# facedancer21.net
KiCad netlist of a schematic drawn in EAGLE
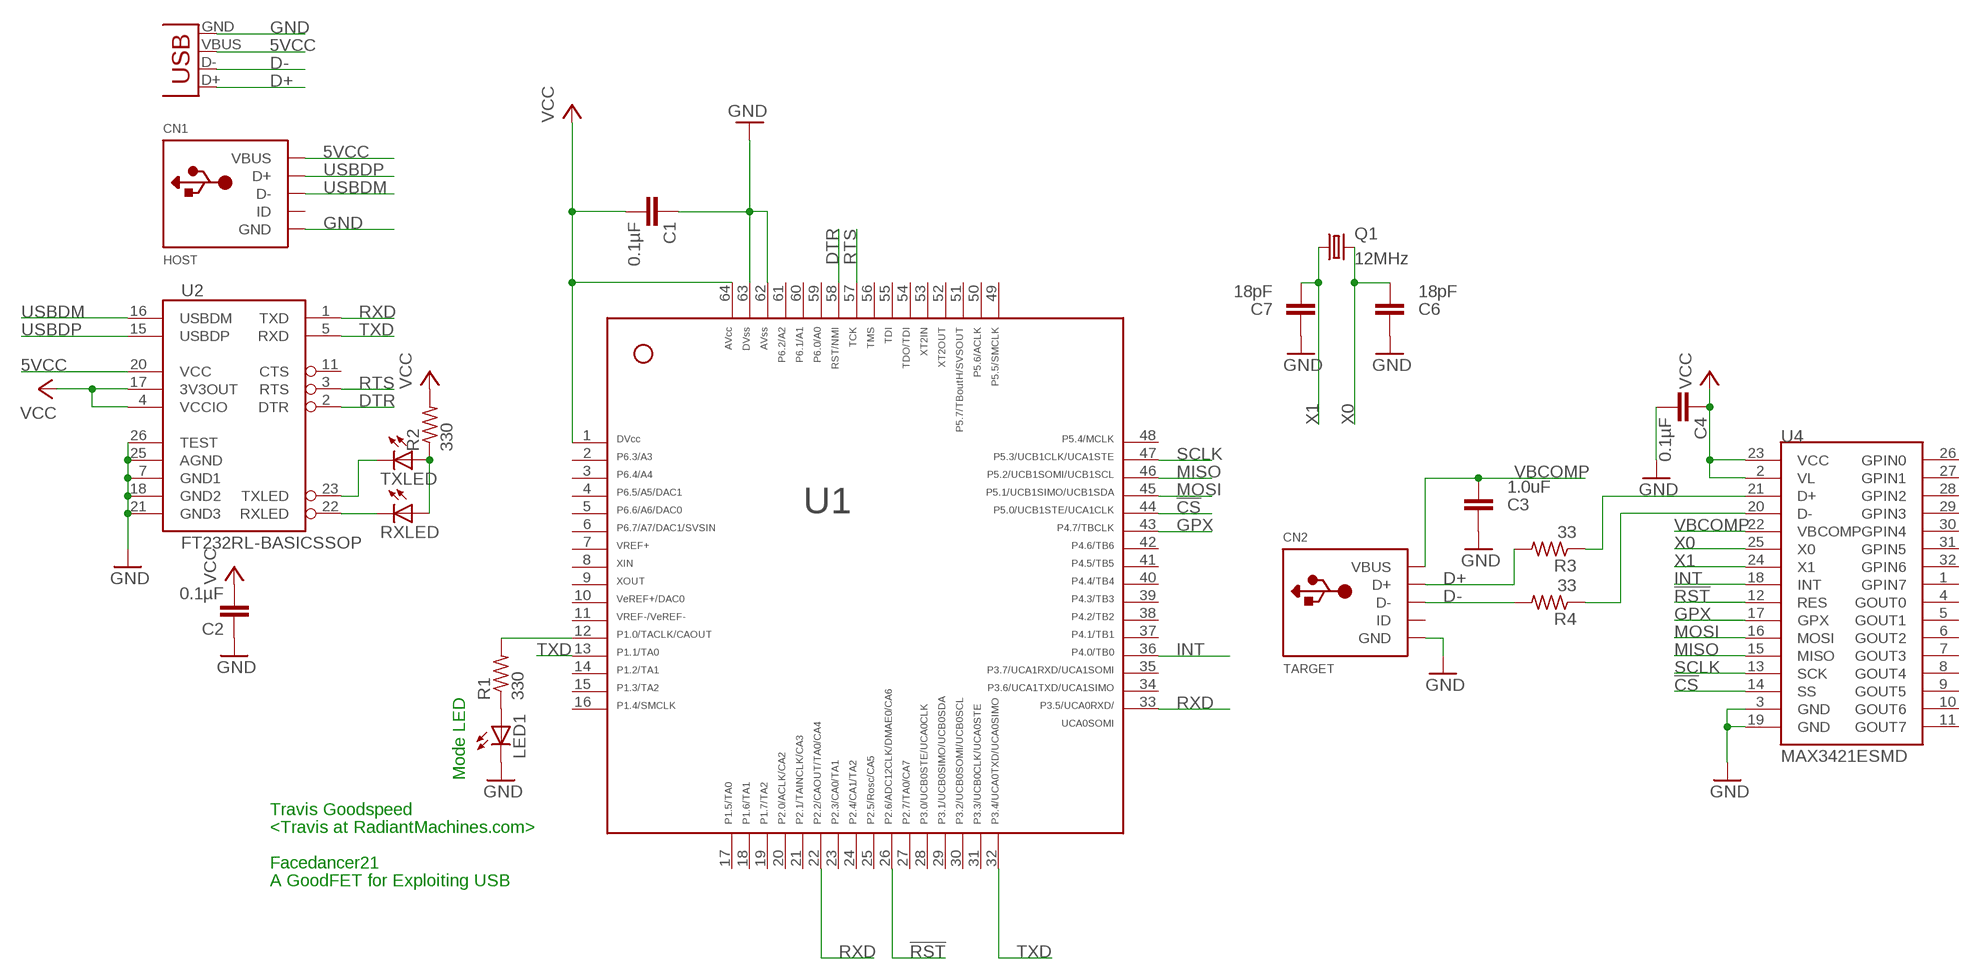
[diagram p0: schematic, sheet 1]

(export (version "E")
  (design (tool "Eeschema 10.0.6"))
  (components
    (comp (ref "C1")
      (value "0.1µF")
      (footprint "eagle-import:C0603")
      (libsource (lib "eagle-import") (part "C-EUC0603"))
    )
    (comp (ref "C2")
      (value "0.1µF")
      (footprint "eagle-import:C0603")
      (libsource (lib "eagle-import") (part "C-EUC0603"))
    )
    (comp (ref "C3")
      (value "1.0uF")
      (footprint "eagle-import:C0603")
      (libsource (lib "eagle-import") (part "C-EUC0603"))
    )
    (comp (ref "C4")
      (value "0.1µF")
      (footprint "eagle-import:C0603")
      (libsource (lib "eagle-import") (part "C-EUC0603"))
    )
    (comp (ref "C6")
      (value "18pF")
      (footprint "eagle-import:C0603")
      (libsource (lib "eagle-import") (part "C-EUC0603"))
    )
    (comp (ref "C7")
      (value "18pF")
      (footprint "eagle-import:C0603")
      (libsource (lib "eagle-import") (part "C-EUC0603"))
    )
    (comp (ref "CN1")
      (value "HOST")
      (footprint "eagle-import:USB-MINIB")
      (libsource (lib "eagle-import") (part "USBMINIB"))
    )
    (comp (ref "CN2")
      (value "TARGET")
      (footprint "eagle-import:USB-MINIB")
      (libsource (lib "eagle-import") (part "USBMINIB"))
    )
    (comp (ref "CN3")
      (value "USB-A-S")
      (footprint "eagle-import:USB-A-S")
      (libsource (lib "eagle-import") (part "USB-A-S"))
    )
    (comp (ref "LED1")
      (value "LEDCHIP-LED0603")
      (footprint "eagle-import:CHIP-LED0603")
      (libsource (lib "eagle-import") (part "LEDCHIP-LED0603"))
    )
    (comp (ref "Q1")
      (value "12MHz")
      (footprint "eagle-import:HC49UP")
      (libsource (lib "eagle-import") (part "CRYSTALHC49UP"))
    )
    (comp (ref "R1")
      (value "330")
      (footprint "eagle-import:R0603")
      (libsource (lib "eagle-import") (part "R-US_R0603"))
    )
    (comp (ref "R2")
      (value "330")
      (footprint "eagle-import:R0603")
      (libsource (lib "eagle-import") (part "R-US_R0603"))
    )
    (comp (ref "R3")
      (value "33")
      (footprint "eagle-import:R0603")
      (libsource (lib "eagle-import") (part "R-US_R0603"))
    )
    (comp (ref "R4")
      (value "33")
      (footprint "eagle-import:R0603")
      (libsource (lib "eagle-import") (part "R-US_R0603"))
    )
    (comp (ref "RXLED")
      (value "LEDCHIP-LED0603")
      (footprint "eagle-import:CHIP-LED0603")
      (libsource (lib "eagle-import") (part "LEDCHIP-LED0603"))
    )
    (comp (ref "TXLED")
      (value "LEDCHIP-LED0603")
      (footprint "eagle-import:CHIP-LED0603")
      (libsource (lib "eagle-import") (part "LEDCHIP-LED0603"))
    )
    (comp (ref "U1")
      (value "F261X---PM64")
      (footprint "eagle-import:PM_PAG64")
      (libsource (lib "eagle-import") (part "F261X---PM64"))
    )
    (comp (ref "U2")
      (value "FT232RL-BASICSSOP")
      (footprint "eagle-import:SSOP28DB")
      (libsource (lib "eagle-import") (part "FT232RL-BASICSSOP"))
    )
    (comp (ref "U4")
      (value "MAX3421ESMD")
      (footprint "eagle-import:TQFP32-5MM")
      (libsource (lib "eagle-import") (part "MAX3421ESMD"))
    )
  )
  (nets
    (net (code "1") (name "/5VCC") (class "Default")
      (node (ref "CN1") (pin "VBUS") (pinfunction "VBUS_VBUS") (pintype "power_in"))
      (node (ref "CN3") (pin "VBUS") (pinfunction "VBUS_VBUS") (pintype "bidirectional"))
      (node (ref "U2") (pin "20") (pinfunction "VCC_20") (pintype "power_in"))
    )
    (net (code "2") (name "/D+") (class "Default")
      (node (ref "CN2") (pin "D+") (pinfunction "D+_D+") (pintype "bidirectional"))
      (node (ref "CN3") (pin "D+") (pinfunction "D+_D+") (pintype "bidirectional"))
      (node (ref "R3") (pin "2") (pinfunction "2_2") (pintype "passive"))
    )
    (net (code "3") (name "/D-") (class "Default")
      (node (ref "CN2") (pin "D-") (pinfunction "D-_D-") (pintype "bidirectional"))
      (node (ref "CN3") (pin "D-") (pinfunction "D-_D-") (pintype "bidirectional"))
      (node (ref "R4") (pin "2") (pinfunction "2_2") (pintype "passive"))
    )
    (net (code "4") (name "/DTR") (class "Default")
      (node (ref "U1") (pin "58") (pinfunction "58_58") (pintype "input"))
      (node (ref "U2") (pin "2") (pinfunction "DTR_2") (pintype "bidirectional"))
    )
    (net (code "5") (name "/GPX") (class "Default")
      (node (ref "U1") (pin "43") (pinfunction "43_43") (pintype "bidirectional"))
      (node (ref "U4") (pin "17") (pinfunction "GPX_17") (pintype "bidirectional"))
    )
    (net (code "6") (name "/INT") (class "Default")
      (node (ref "U1") (pin "36") (pinfunction "36_36") (pintype "output"))
      (node (ref "U4") (pin "18") (pinfunction "INT_18") (pintype "bidirectional"))
    )
    (net (code "7") (name "/MISO") (class "Default")
      (node (ref "U1") (pin "46") (pinfunction "46_46") (pintype "bidirectional"))
      (node (ref "U4") (pin "15") (pinfunction "MISO_15") (pintype "bidirectional"))
    )
    (net (code "8") (name "/MOSI") (class "Default")
      (node (ref "U1") (pin "45") (pinfunction "45_45") (pintype "bidirectional"))
      (node (ref "U4") (pin "16") (pinfunction "MOSI_16") (pintype "bidirectional"))
    )
    (net (code "9") (name "/RTS") (class "Default")
      (node (ref "U1") (pin "57") (pinfunction "57_57") (pintype "input"))
      (node (ref "U2") (pin "3") (pinfunction "RTS_3") (pintype "bidirectional"))
    )
    (net (code "10") (name "/RXD") (class "Default")
      (node (ref "U1") (pin "22") (pinfunction "22_22") (pintype "bidirectional"))
      (node (ref "U1") (pin "33") (pinfunction "33_33") (pintype "bidirectional"))
      (node (ref "U2") (pin "1") (pinfunction "TXD_1") (pintype "output"))
    )
    (net (code "11") (name "/SCLK") (class "Default")
      (node (ref "U1") (pin "47") (pinfunction "47_47") (pintype "bidirectional"))
      (node (ref "U4") (pin "13") (pinfunction "SCK_13") (pintype "bidirectional"))
    )
    (net (code "12") (name "/TXD") (class "Default")
      (node (ref "U1") (pin "13") (pinfunction "13_13") (pintype "bidirectional"))
      (node (ref "U1") (pin "32") (pinfunction "32_32") (pintype "bidirectional"))
      (node (ref "U2") (pin "5") (pinfunction "RXD_5") (pintype "input"))
    )
    (net (code "13") (name "/USBDM") (class "Default")
      (node (ref "CN1") (pin "D-") (pinfunction "D-_D-") (pintype "bidirectional"))
      (node (ref "U2") (pin "16") (pinfunction "USBDM_16") (pintype "bidirectional"))
    )
    (net (code "14") (name "/USBDP") (class "Default")
      (node (ref "CN1") (pin "D+") (pinfunction "D+_D+") (pintype "bidirectional"))
      (node (ref "U2") (pin "15") (pinfunction "USBDP_15") (pintype "bidirectional"))
    )
    (net (code "15") (name "/VBCOMP") (class "Default")
      (node (ref "C3") (pin "2") (pinfunction "2_2") (pintype "passive"))
      (node (ref "CN2") (pin "VBUS") (pinfunction "VBUS_VBUS") (pintype "power_in"))
      (node (ref "U4") (pin "22") (pinfunction "VBCOMP_22") (pintype "bidirectional"))
    )
    (net (code "16") (name "/X0") (class "Default")
      (node (ref "C6") (pin "2") (pinfunction "2_2") (pintype "passive"))
      (node (ref "Q1") (pin "2") (pinfunction "2_2") (pintype "passive"))
      (node (ref "U4") (pin "25") (pinfunction "X0_25") (pintype "bidirectional"))
    )
    (net (code "17") (name "/X1") (class "Default")
      (node (ref "C7") (pin "2") (pinfunction "2_2") (pintype "passive"))
      (node (ref "Q1") (pin "1") (pinfunction "1_1") (pintype "passive"))
      (node (ref "U4") (pin "24") (pinfunction "X1_24") (pintype "bidirectional"))
    )
    (net (code "18") (name "/~{CS}") (class "Default")
      (node (ref "U1") (pin "44") (pinfunction "44_44") (pintype "bidirectional"))
      (node (ref "U4") (pin "14") (pinfunction "SS_14") (pintype "bidirectional"))
    )
    (net (code "19") (name "/~{RST}") (class "Default")
      (node (ref "U1") (pin "26") (pinfunction "26_26") (pintype "bidirectional"))
      (node (ref "U4") (pin "12") (pinfunction "RES_12") (pintype "bidirectional"))
    )
    (net (code "20") (name "GND") (class "Default")
      (node (ref "C1") (pin "1") (pinfunction "1_1") (pintype "passive"))
      (node (ref "C2") (pin "1") (pinfunction "1_1") (pintype "passive"))
      (node (ref "C3") (pin "1") (pinfunction "1_1") (pintype "passive"))
      (node (ref "C4") (pin "2") (pinfunction "2_2") (pintype "passive"))
      (node (ref "C6") (pin "1") (pinfunction "1_1") (pintype "passive"))
      (node (ref "C7") (pin "1") (pinfunction "1_1") (pintype "passive"))
      (node (ref "CN1") (pin "GND") (pinfunction "GND_GND") (pintype "power_in"))
      (node (ref "CN2") (pin "GND") (pinfunction "GND_GND") (pintype "power_in"))
      (node (ref "CN3") (pin "GND") (pinfunction "GND_GND") (pintype "bidirectional"))
      (node (ref "LED1") (pin "C") (pinfunction "C_C") (pintype "passive"))
      (node (ref "U1") (pin "62") (pinfunction "62_62") (pintype "power_in"))
      (node (ref "U1") (pin "63") (pinfunction "63_63") (pintype "power_in"))
      (node (ref "U2") (pin "18") (pinfunction "GND2_18") (pintype "power_in"))
      (node (ref "U2") (pin "21") (pinfunction "GND3_21") (pintype "power_in"))
      (node (ref "U2") (pin "25") (pinfunction "AGND_25") (pintype "power_in"))
      (node (ref "U2") (pin "26") (pinfunction "TEST_26") (pintype "input"))
      (node (ref "U2") (pin "7") (pinfunction "GND1_7") (pintype "power_in"))
      (node (ref "U4") (pin "19") (pinfunction "GND_19") (pintype "bidirectional"))
      (node (ref "U4") (pin "3") (pinfunction "GND_3") (pintype "bidirectional"))
    )
    (net (code "21") (name "Net-(LED1-PadA)") (class "Default")
      (node (ref "LED1") (pin "A") (pinfunction "A_A") (pintype "passive"))
      (node (ref "R1") (pin "1") (pinfunction "1_1") (pintype "passive"))
    )
    (net (code "22") (name "Net-(R1-Pad2)") (class "Default")
      (node (ref "R1") (pin "2") (pinfunction "2_2") (pintype "passive"))
      (node (ref "U1") (pin "12") (pinfunction "12_12") (pintype "bidirectional"))
    )
    (net (code "23") (name "Net-(R2-Pad1)") (class "Default")
      (node (ref "R2") (pin "1") (pinfunction "1_1") (pintype "passive"))
      (node (ref "RXLED") (pin "A") (pinfunction "A_A") (pintype "passive"))
      (node (ref "TXLED") (pin "A") (pinfunction "A_A") (pintype "passive"))
    )
    (net (code "24") (name "Net-(U2-RXLED)") (class "Default")
      (node (ref "RXLED") (pin "C") (pinfunction "C_C") (pintype "passive"))
      (node (ref "U2") (pin "22") (pinfunction "RXLED_22") (pintype "bidirectional"))
    )
    (net (code "25") (name "Net-(U2-TXLED)") (class "Default")
      (node (ref "TXLED") (pin "C") (pinfunction "C_C") (pintype "passive"))
      (node (ref "U2") (pin "23") (pinfunction "TXLED_23") (pintype "bidirectional"))
    )
    (net (code "26") (name "Net-(U4-D+)") (class "Default")
      (node (ref "R3") (pin "1") (pinfunction "1_1") (pintype "passive"))
      (node (ref "U4") (pin "21") (pinfunction "D+_21") (pintype "bidirectional"))
    )
    (net (code "27") (name "Net-(U4-D-)") (class "Default")
      (node (ref "R4") (pin "1") (pinfunction "1_1") (pintype "passive"))
      (node (ref "U4") (pin "20") (pinfunction "D-_20") (pintype "bidirectional"))
    )
    (net (code "28") (name "VCC") (class "Default")
      (node (ref "C1") (pin "2") (pinfunction "2_2") (pintype "passive"))
      (node (ref "C2") (pin "2") (pinfunction "2_2") (pintype "passive"))
      (node (ref "C4") (pin "1") (pinfunction "1_1") (pintype "passive"))
      (node (ref "R2") (pin "2") (pinfunction "2_2") (pintype "passive"))
      (node (ref "U1") (pin "1") (pinfunction "1_1") (pintype "power_in"))
      (node (ref "U1") (pin "64") (pinfunction "64_64") (pintype "power_in"))
      (node (ref "U2") (pin "17") (pinfunction "3V3OUT_17") (pintype "output"))
      (node (ref "U2") (pin "4") (pinfunction "VCCIO_4") (pintype "power_in"))
      (node (ref "U4") (pin "2") (pinfunction "VL_2") (pintype "bidirectional"))
      (node (ref "U4") (pin "23") (pinfunction "VCC_23") (pintype "bidirectional"))
    )
    (net (code "29") (name "unconnected-(CN1-PadID)") (class "Default")
      (node (ref "CN1") (pin "ID") (pinfunction "ID_ID") (pintype "bidirectional"))
    )
    (net (code "30") (name "unconnected-(CN2-PadID)") (class "Default")
      (node (ref "CN2") (pin "ID") (pinfunction "ID_ID") (pintype "bidirectional"))
    )
    (net (code "31") (name "unconnected-(U1-Pad2)") (class "Default")
      (node (ref "U1") (pin "2") (pinfunction "2_2") (pintype "bidirectional"))
    )
    (net (code "32") (name "unconnected-(U1-Pad3)") (class "Default")
      (node (ref "U1") (pin "3") (pinfunction "3_3") (pintype "bidirectional"))
    )
    (net (code "33") (name "unconnected-(U1-Pad4)") (class "Default")
      (node (ref "U1") (pin "4") (pinfunction "4_4") (pintype "bidirectional"))
    )
    (net (code "34") (name "unconnected-(U1-Pad5)") (class "Default")
      (node (ref "U1") (pin "5") (pinfunction "5_5") (pintype "bidirectional"))
    )
    (net (code "35") (name "unconnected-(U1-Pad6)") (class "Default")
      (node (ref "U1") (pin "6") (pinfunction "6_6") (pintype "bidirectional"))
    )
    (net (code "36") (name "unconnected-(U1-Pad7)") (class "Default")
      (node (ref "U1") (pin "7") (pinfunction "7_7") (pintype "output"))
    )
    (net (code "37") (name "unconnected-(U1-Pad8)") (class "Default")
      (node (ref "U1") (pin "8") (pinfunction "8_8") (pintype "input"))
    )
    (net (code "38") (name "unconnected-(U1-Pad9)") (class "Default")
      (node (ref "U1") (pin "9") (pinfunction "9_9") (pintype "output"))
    )
    (net (code "39") (name "unconnected-(U1-Pad10)") (class "Default")
      (node (ref "U1") (pin "10") (pinfunction "10_10") (pintype "bidirectional"))
    )
    (net (code "40") (name "unconnected-(U1-Pad11)") (class "Default")
      (node (ref "U1") (pin "11") (pinfunction "11_11") (pintype "bidirectional"))
    )
    (net (code "41") (name "unconnected-(U1-Pad14)") (class "Default")
      (node (ref "U1") (pin "14") (pinfunction "14_14") (pintype "bidirectional"))
    )
    (net (code "42") (name "unconnected-(U1-Pad15)") (class "Default")
      (node (ref "U1") (pin "15") (pinfunction "15_15") (pintype "bidirectional"))
    )
    (net (code "43") (name "unconnected-(U1-Pad16)") (class "Default")
      (node (ref "U1") (pin "16") (pinfunction "16_16") (pintype "bidirectional"))
    )
    (net (code "44") (name "unconnected-(U1-Pad17)") (class "Default")
      (node (ref "U1") (pin "17") (pinfunction "17_17") (pintype "bidirectional"))
    )
    (net (code "45") (name "unconnected-(U1-Pad18)") (class "Default")
      (node (ref "U1") (pin "18") (pinfunction "18_18") (pintype "bidirectional"))
    )
    (net (code "46") (name "unconnected-(U1-Pad19)") (class "Default")
      (node (ref "U1") (pin "19") (pinfunction "19_19") (pintype "bidirectional"))
    )
    (net (code "47") (name "unconnected-(U1-Pad20)") (class "Default")
      (node (ref "U1") (pin "20") (pinfunction "20_20") (pintype "bidirectional"))
    )
    (net (code "48") (name "unconnected-(U1-Pad21)") (class "Default")
      (node (ref "U1") (pin "21") (pinfunction "21_21") (pintype "bidirectional"))
    )
    (net (code "49") (name "unconnected-(U1-Pad23)") (class "Default")
      (node (ref "U1") (pin "23") (pinfunction "23_23") (pintype "bidirectional"))
    )
    (net (code "50") (name "unconnected-(U1-Pad24)") (class "Default")
      (node (ref "U1") (pin "24") (pinfunction "24_24") (pintype "bidirectional"))
    )
    (net (code "51") (name "unconnected-(U1-Pad25)") (class "Default")
      (node (ref "U1") (pin "25") (pinfunction "25_25") (pintype "bidirectional"))
    )
    (net (code "52") (name "unconnected-(U1-Pad27)") (class "Default")
      (node (ref "U1") (pin "27") (pinfunction "27_27") (pintype "bidirectional"))
    )
    (net (code "53") (name "unconnected-(U1-Pad28)") (class "Default")
      (node (ref "U1") (pin "28") (pinfunction "28_28") (pintype "bidirectional"))
    )
    (net (code "54") (name "unconnected-(U1-Pad29)") (class "Default")
      (node (ref "U1") (pin "29") (pinfunction "29_29") (pintype "bidirectional"))
    )
    (net (code "55") (name "unconnected-(U1-Pad30)") (class "Default")
      (node (ref "U1") (pin "30") (pinfunction "30_30") (pintype "bidirectional"))
    )
    (net (code "56") (name "unconnected-(U1-Pad31)") (class "Default")
      (node (ref "U1") (pin "31") (pinfunction "31_31") (pintype "bidirectional"))
    )
    (net (code "57") (name "unconnected-(U1-Pad34)") (class "Default")
      (node (ref "U1") (pin "34") (pinfunction "34_34") (pintype "bidirectional"))
    )
    (net (code "58") (name "unconnected-(U1-Pad35)") (class "Default")
      (node (ref "U1") (pin "35") (pinfunction "35_35") (pintype "bidirectional"))
    )
    (net (code "59") (name "unconnected-(U1-Pad37)") (class "Default")
      (node (ref "U1") (pin "37") (pinfunction "37_37") (pintype "bidirectional"))
    )
    (net (code "60") (name "unconnected-(U1-Pad38)") (class "Default")
      (node (ref "U1") (pin "38") (pinfunction "38_38") (pintype "bidirectional"))
    )
    (net (code "61") (name "unconnected-(U1-Pad39)") (class "Default")
      (node (ref "U1") (pin "39") (pinfunction "39_39") (pintype "bidirectional"))
    )
    (net (code "62") (name "unconnected-(U1-Pad40)") (class "Default")
      (node (ref "U1") (pin "40") (pinfunction "40_40") (pintype "input"))
    )
    (net (code "63") (name "unconnected-(U1-Pad41)") (class "Default")
      (node (ref "U1") (pin "41") (pinfunction "41_41") (pintype "bidirectional"))
    )
    (net (code "64") (name "unconnected-(U1-Pad42)") (class "Default")
      (node (ref "U1") (pin "42") (pinfunction "42_42") (pintype "bidirectional"))
    )
    (net (code "65") (name "unconnected-(U1-Pad48)") (class "Default")
      (node (ref "U1") (pin "48") (pinfunction "48_48") (pintype "bidirectional"))
    )
    (net (code "66") (name "unconnected-(U1-Pad49)") (class "Default")
      (node (ref "U1") (pin "49") (pinfunction "49_49") (pintype "bidirectional"))
    )
    (net (code "67") (name "unconnected-(U1-Pad50)") (class "Default")
      (node (ref "U1") (pin "50") (pinfunction "50_50") (pintype "bidirectional"))
    )
    (net (code "68") (name "unconnected-(U1-Pad51)") (class "Default")
      (node (ref "U1") (pin "51") (pinfunction "51_51") (pintype "bidirectional"))
    )
    (net (code "69") (name "unconnected-(U1-Pad52)") (class "Default")
      (node (ref "U1") (pin "52") (pinfunction "52_52") (pintype "output"))
    )
    (net (code "70") (name "unconnected-(U1-Pad53)") (class "Default")
      (node (ref "U1") (pin "53") (pinfunction "53_53") (pintype "input"))
    )
    (net (code "71") (name "unconnected-(U1-Pad54)") (class "Default")
      (node (ref "U1") (pin "54") (pinfunction "54_54") (pintype "bidirectional"))
    )
    (net (code "72") (name "unconnected-(U1-Pad55)") (class "Default")
      (node (ref "U1") (pin "55") (pinfunction "55_55") (pintype "input"))
    )
    (net (code "73") (name "unconnected-(U1-Pad56)") (class "Default")
      (node (ref "U1") (pin "56") (pinfunction "56_56") (pintype "input"))
    )
    (net (code "74") (name "unconnected-(U1-Pad59)") (class "Default")
      (node (ref "U1") (pin "59") (pinfunction "59_59") (pintype "bidirectional"))
    )
    (net (code "75") (name "unconnected-(U1-Pad60)") (class "Default")
      (node (ref "U1") (pin "60") (pinfunction "60_60") (pintype "bidirectional"))
    )
    (net (code "76") (name "unconnected-(U1-Pad61)") (class "Default")
      (node (ref "U1") (pin "61") (pinfunction "61_61") (pintype "bidirectional"))
    )
    (net (code "77") (name "unconnected-(U2-CTS-Pad11)") (class "Default")
      (node (ref "U2") (pin "11") (pinfunction "CTS_11") (pintype "bidirectional"))
    )
    (net (code "78") (name "unconnected-(U4-GOUT0-Pad4)") (class "Default")
      (node (ref "U4") (pin "4") (pinfunction "GOUT0_4") (pintype "bidirectional"))
    )
    (net (code "79") (name "unconnected-(U4-GOUT1-Pad5)") (class "Default")
      (node (ref "U4") (pin "5") (pinfunction "GOUT1_5") (pintype "bidirectional"))
    )
    (net (code "80") (name "unconnected-(U4-GOUT2-Pad6)") (class "Default")
      (node (ref "U4") (pin "6") (pinfunction "GOUT2_6") (pintype "bidirectional"))
    )
    (net (code "81") (name "unconnected-(U4-GOUT3-Pad7)") (class "Default")
      (node (ref "U4") (pin "7") (pinfunction "GOUT3_7") (pintype "bidirectional"))
    )
    (net (code "82") (name "unconnected-(U4-GOUT4-Pad8)") (class "Default")
      (node (ref "U4") (pin "8") (pinfunction "GOUT4_8") (pintype "bidirectional"))
    )
    (net (code "83") (name "unconnected-(U4-GOUT5-Pad9)") (class "Default")
      (node (ref "U4") (pin "9") (pinfunction "GOUT5_9") (pintype "bidirectional"))
    )
    (net (code "84") (name "unconnected-(U4-GOUT6-Pad10)") (class "Default")
      (node (ref "U4") (pin "10") (pinfunction "GOUT6_10") (pintype "bidirectional"))
    )
    (net (code "85") (name "unconnected-(U4-GOUT7-Pad11)") (class "Default")
      (node (ref "U4") (pin "11") (pinfunction "GOUT7_11") (pintype "bidirectional"))
    )
    (net (code "86") (name "unconnected-(U4-GPIN0-Pad26)") (class "Default")
      (node (ref "U4") (pin "26") (pinfunction "GPIN0_26") (pintype "bidirectional"))
    )
    (net (code "87") (name "unconnected-(U4-GPIN1-Pad27)") (class "Default")
      (node (ref "U4") (pin "27") (pinfunction "GPIN1_27") (pintype "bidirectional"))
    )
    (net (code "88") (name "unconnected-(U4-GPIN2-Pad28)") (class "Default")
      (node (ref "U4") (pin "28") (pinfunction "GPIN2_28") (pintype "bidirectional"))
    )
    (net (code "89") (name "unconnected-(U4-GPIN3-Pad29)") (class "Default")
      (node (ref "U4") (pin "29") (pinfunction "GPIN3_29") (pintype "bidirectional"))
    )
    (net (code "90") (name "unconnected-(U4-GPIN4-Pad30)") (class "Default")
      (node (ref "U4") (pin "30") (pinfunction "GPIN4_30") (pintype "bidirectional"))
    )
    (net (code "91") (name "unconnected-(U4-GPIN5-Pad31)") (class "Default")
      (node (ref "U4") (pin "31") (pinfunction "GPIN5_31") (pintype "bidirectional"))
    )
    (net (code "92") (name "unconnected-(U4-GPIN6-Pad32)") (class "Default")
      (node (ref "U4") (pin "32") (pinfunction "GPIN6_32") (pintype "bidirectional"))
    )
    (net (code "93") (name "unconnected-(U4-GPIN7-Pad1)") (class "Default")
      (node (ref "U4") (pin "1") (pinfunction "GPIN7_1") (pintype "bidirectional"))
    )
  )
)
